# MicroMod-LoRa-1W-Function-Board-Waterfal.net
KiCad netlist of a schematic drawn in EAGLE
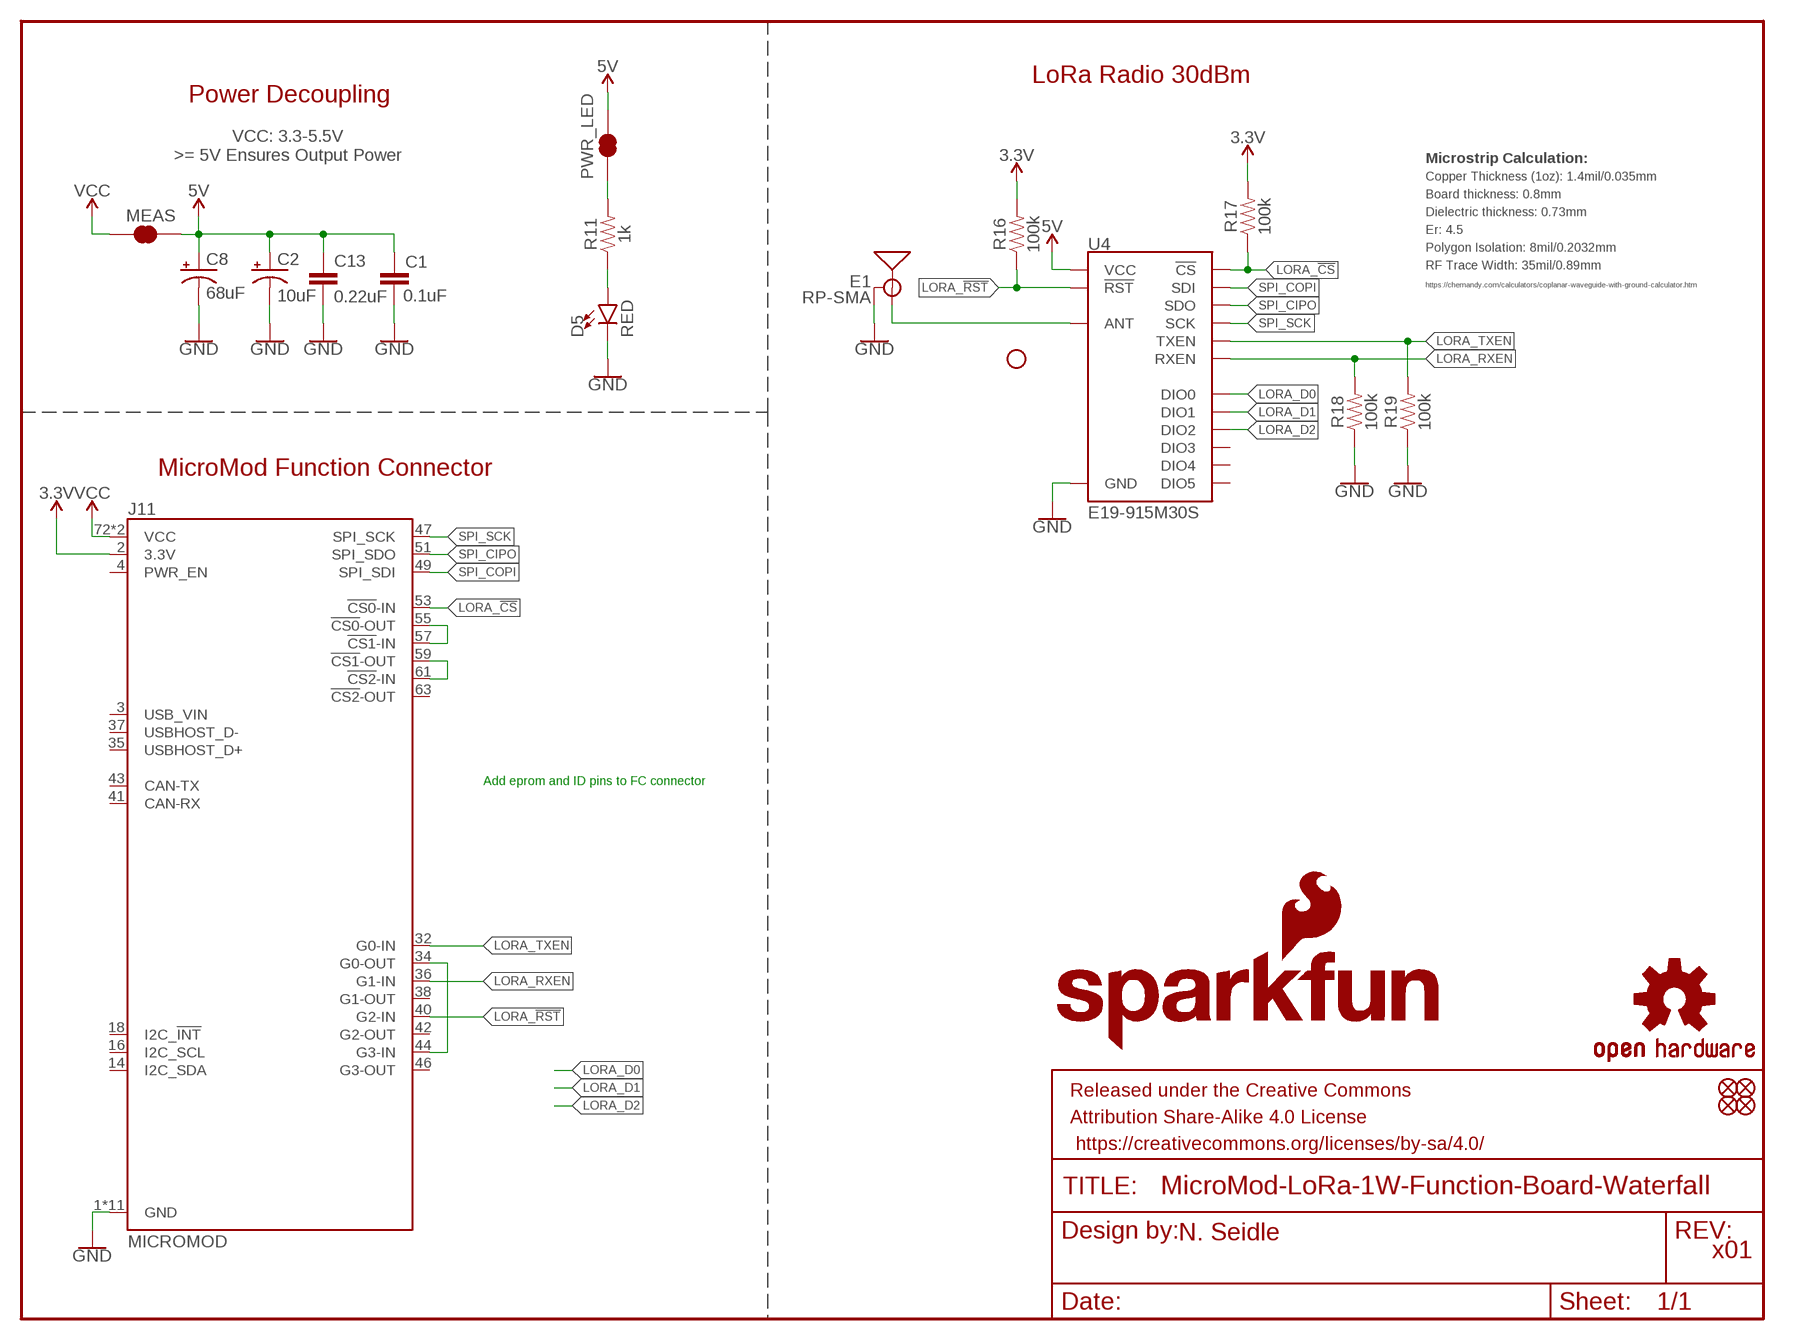
[diagram p0: schematic, sheet 1]

(export (version "E")
  (design (tool "Eeschema 10.0.6"))
  (components
    (comp (ref "C1")
      (value "0.1uF")
      (footprint "eagle-import:0603")
      (libsource (lib "eagle-import") (part "0.1UF-0603-25V-(+80/-20%)"))
    )
    (comp (ref "C2")
      (value "10uF")
      (footprint "eagle-import:EIA3216")
      (libsource (lib "eagle-import") (part "10UF-POLAR-EIA3216-16V-10%(TANT)"))
    )
    (comp (ref "C8")
      (value "68uF")
      (footprint "eagle-import:EIA3528")
      (libsource (lib "eagle-import") (part "68UF-POLAR-EIA3528-10V-10%(TANT)"))
    )
    (comp (ref "C13")
      (value "0.22uF")
      (footprint "eagle-import:0603")
      (libsource (lib "eagle-import") (part "0.22UF-0603-25V-10%"))
    )
    (comp (ref "D5")
      (value "RED")
      (footprint "eagle-import:LED-0603")
      (libsource (lib "eagle-import") (part "LED-RED0603"))
    )
    (comp (ref "E1")
      (value "RP-SMA")
      (footprint "eagle-import:SMA-EDGE-SMD")
      (libsource (lib "eagle-import") (part "ANTENNA-SMA-GROUNDEDEDGE_RPSMA_SMD"))
    )
    (comp (ref "FD1")
      (value "FIDUCIALUFIDUCIAL")
      (footprint "eagle-import:FIDUCIAL-MICRO")
      (libsource (lib "eagle-import") (part "FIDUCIALUFIDUCIAL"))
    )
    (comp (ref "FD2")
      (value "FIDUCIALUFIDUCIAL")
      (footprint "eagle-import:FIDUCIAL-MICRO")
      (libsource (lib "eagle-import") (part "FIDUCIALUFIDUCIAL"))
    )
    (comp (ref "FD3")
      (value "FIDUCIALUFIDUCIAL")
      (footprint "eagle-import:FIDUCIAL-MICRO")
      (libsource (lib "eagle-import") (part "FIDUCIALUFIDUCIAL"))
    )
    (comp (ref "FD4")
      (value "FIDUCIALUFIDUCIAL")
      (footprint "eagle-import:FIDUCIAL-MICRO")
      (libsource (lib "eagle-import") (part "FIDUCIALUFIDUCIAL"))
    )
    (comp (ref "FRAME2")
      (value "FRAME-LETTER")
      (footprint "eagle-import:CREATIVE_COMMONS")
      (libsource (lib "eagle-import") (part "FRAME-LETTER"))
    )
    (comp (ref "H1")
      (value "STAND-OFF")
      (footprint "eagle-import:STAND-OFF")
      (libsource (lib "eagle-import") (part "STAND-OFF"))
    )
    (comp (ref "J11")
      (value "MICROMOD")
      (footprint "eagle-import:M.2-CARD-E-22_FUNCTION_STANDARD")
      (libsource (lib "eagle-import") (part "MICROMOD"))
    )
    (comp (ref "LOGO1")
      (value "SFE_LOGO_NAME_FLAME.1_INCH")
      (footprint "eagle-import:SFE_LOGO_NAME_FLAME_.1")
      (libsource (lib "eagle-import") (part "SFE_LOGO_NAME_FLAME.1_INCH"))
    )
    (comp (ref "LOGO3")
      (value "OSHW-LOGOMINI")
      (footprint "eagle-import:OSHW-LOGO-MINI")
      (libsource (lib "eagle-import") (part "OSHW-LOGOMINI"))
    )
    (comp (ref "MEAS")
      (value "JUMPER-COMBO_2_NC_TRACE")
      (footprint "eagle-import:COMBO-JUMPER_2_NC_TRACE")
      (libsource (lib "eagle-import") (part "JUMPER-COMBO_2_NC_TRACE"))
    )
    (comp (ref "PWR_LED")
      (value "JUMPER-SMT_2_NC_TRACE_SILK")
      (footprint "eagle-import:SMT-JUMPER_2_NC_TRACE_SILK")
      (libsource (lib "eagle-import") (part "JUMPER-SMT_2_NC_TRACE_SILK"))
    )
    (comp (ref "R11")
      (value "1k")
      (footprint "eagle-import:0603")
      (libsource (lib "eagle-import") (part "1KOHM-0603-1/10W-1%"))
    )
    (comp (ref "R16")
      (value "100k")
      (footprint "eagle-import:0603")
      (libsource (lib "eagle-import") (part "100KOHM-0603-1/10W-1%"))
    )
    (comp (ref "R17")
      (value "100k")
      (footprint "eagle-import:0603")
      (libsource (lib "eagle-import") (part "100KOHM-0603-1/10W-1%"))
    )
    (comp (ref "R18")
      (value "100k")
      (footprint "eagle-import:0603")
      (libsource (lib "eagle-import") (part "100KOHM-0603-1/10W-1%"))
    )
    (comp (ref "R19")
      (value "100k")
      (footprint "eagle-import:0603")
      (libsource (lib "eagle-import") (part "100KOHM-0603-1/10W-1%"))
    )
    (comp (ref "U4")
      (value "E19-915M30S")
      (footprint "eagle-import:E19-915MS1W")
      (libsource (lib "eagle-import") (part "E19-915MS1W"))
    )
  )
  (nets
    (net (code "1") (name "/LORA_~{CS}") (class "Default")
      (node (ref "J11") (pin "53") (pinfunction "~{CS0}-IN_53") (pintype "bidirectional"))
      (node (ref "R17") (pin "1") (pinfunction "1_1") (pintype "passive"))
      (node (ref "U4") (pin "15") (pinfunction "~{CS}_15") (pintype "bidirectional"))
    )
    (net (code "2") (name "/LORA_~{RST}") (class "Default")
      (node (ref "J11") (pin "40") (pinfunction "G2-IN_40") (pintype "bidirectional"))
      (node (ref "R16") (pin "1") (pinfunction "1_1") (pintype "passive"))
      (node (ref "U4") (pin "8") (pinfunction "~{RST}_8") (pintype "bidirectional"))
    )
    (net (code "3") (name "3.3V") (class "Default")
      (node (ref "J11") (pin "2") (pinfunction "3.3V_2") (pintype "bidirectional"))
      (node (ref "R16") (pin "2") (pinfunction "2_2") (pintype "passive"))
      (node (ref "R17") (pin "2") (pinfunction "2_2") (pintype "passive"))
    )
    (net (code "4") (name "5V") (class "Default")
      (node (ref "C1") (pin "1") (pinfunction "1_1") (pintype "passive"))
      (node (ref "C13") (pin "1") (pinfunction "1_1") (pintype "passive"))
      (node (ref "C2") (pin "+") (pinfunction "+_+") (pintype "passive"))
      (node (ref "C8") (pin "A") (pinfunction "+_A") (pintype "passive"))
      (node (ref "MEAS") (pin "2") (pinfunction "2_2") (pintype "passive"))
      (node (ref "MEAS") (pin "4") (pinfunction "2_4") (pintype "passive"))
      (node (ref "PWR_LED") (pin "2") (pinfunction "2_2") (pintype "passive"))
      (node (ref "U4") (pin "11") (pinfunction "VCC_11") (pintype "bidirectional"))
    )
    (net (code "5") (name "GND") (class "Default")
      (node (ref "C1") (pin "2") (pinfunction "2_2") (pintype "passive"))
      (node (ref "C13") (pin "2") (pinfunction "2_2") (pintype "passive"))
      (node (ref "C2") (pin "-") (pinfunction "-_-") (pintype "passive"))
      (node (ref "C8") (pin "C") (pinfunction "-_C") (pintype "passive"))
      (node (ref "D5") (pin "C") (pinfunction "C_C") (pintype "passive"))
      (node (ref "E1") (pin "GND@0") (pinfunction "GND_GND@0") (pintype "bidirectional"))
      (node (ref "E1") (pin "GND@1") (pinfunction "GND_GND@1") (pintype "bidirectional"))
      (node (ref "J11") (pin "1") (pinfunction "GND_1") (pintype "bidirectional"))
      (node (ref "J11") (pin "33") (pinfunction "GND_33") (pintype "bidirectional"))
      (node (ref "J11") (pin "39") (pinfunction "GND_39") (pintype "bidirectional"))
      (node (ref "J11") (pin "45") (pinfunction "GND_45") (pintype "bidirectional"))
      (node (ref "J11") (pin "75") (pinfunction "GND_75") (pintype "bidirectional"))
      (node (ref "J11") (pin "GND1") (pinfunction "GND_GND1") (pintype "bidirectional"))
      (node (ref "J11") (pin "GND2") (pinfunction "GND_GND2") (pintype "bidirectional"))
      (node (ref "J11") (pin "GND3") (pinfunction "GND_GND3") (pintype "bidirectional"))
      (node (ref "J11") (pin "GND4") (pinfunction "GND_GND4") (pintype "bidirectional"))
      (node (ref "J11") (pin "GND5") (pinfunction "GND_GND5") (pintype "bidirectional"))
      (node (ref "J11") (pin "GND6") (pinfunction "GND_GND6") (pintype "bidirectional"))
      (node (ref "R18") (pin "1") (pinfunction "1_1") (pintype "passive"))
      (node (ref "R19") (pin "1") (pinfunction "1_1") (pintype "passive"))
      (node (ref "U4") (pin "1") (pinfunction "GND_1") (pintype "bidirectional"))
      (node (ref "U4") (pin "10") (pinfunction "GND_10") (pintype "bidirectional"))
      (node (ref "U4") (pin "18") (pinfunction "GND_18") (pintype "bidirectional"))
      (node (ref "U4") (pin "20") (pinfunction "GND_20") (pintype "bidirectional"))
      (node (ref "U4") (pin "21") (pinfunction "GND_21") (pintype "bidirectional"))
      (node (ref "U4") (pin "22") (pinfunction "GND_22") (pintype "bidirectional"))
      (node (ref "U4") (pin "9") (pinfunction "GND_9") (pintype "bidirectional"))
    )
    (net (code "6") (name "LORA_D0") (class "Default")
      (node (ref "U4") (pin "7") (pinfunction "DIO0_7") (pintype "bidirectional"))
    )
    (net (code "7") (name "LORA_D1") (class "Default")
      (node (ref "U4") (pin "6") (pinfunction "DIO1_6") (pintype "bidirectional"))
    )
    (net (code "8") (name "LORA_D2") (class "Default")
      (node (ref "U4") (pin "5") (pinfunction "DIO2_5") (pintype "bidirectional"))
    )
    (net (code "9") (name "LORA_RXEN") (class "Default")
      (node (ref "J11") (pin "36") (pinfunction "G1-IN_36") (pintype "bidirectional"))
      (node (ref "R18") (pin "2") (pinfunction "2_2") (pintype "passive"))
      (node (ref "U4") (pin "17") (pinfunction "RXEN_17") (pintype "bidirectional"))
    )
    (net (code "10") (name "LORA_TXEN") (class "Default")
      (node (ref "J11") (pin "32") (pinfunction "G0-IN_32") (pintype "bidirectional"))
      (node (ref "R19") (pin "2") (pinfunction "2_2") (pintype "passive"))
      (node (ref "U4") (pin "16") (pinfunction "TXEN_16") (pintype "bidirectional"))
    )
    (net (code "11") (name "Net-(D5-PadA)") (class "Default")
      (node (ref "D5") (pin "A") (pinfunction "A_A") (pintype "passive"))
      (node (ref "R11") (pin "1") (pinfunction "1_1") (pintype "passive"))
    )
    (net (code "12") (name "Net-(E1-SIGNAL)") (class "Default")
      (node (ref "E1") (pin "SIG") (pinfunction "SIGNAL_SIG") (pintype "bidirectional"))
      (node (ref "U4") (pin "19") (pinfunction "ANT_19") (pintype "bidirectional"))
    )
    (net (code "13") (name "Net-(J11-G0-OUT)") (class "Default")
      (node (ref "J11") (pin "34") (pinfunction "G0-OUT_34") (pintype "bidirectional"))
      (node (ref "J11") (pin "44") (pinfunction "G3-IN_44") (pintype "bidirectional"))
    )
    (net (code "14") (name "Net-(J11-~{CS0}-OUT)") (class "Default")
      (node (ref "J11") (pin "55") (pinfunction "~{CS0}-OUT_55") (pintype "bidirectional"))
      (node (ref "J11") (pin "57") (pinfunction "~{CS1}-IN_57") (pintype "bidirectional"))
    )
    (net (code "15") (name "Net-(J11-~{CS1}-OUT)") (class "Default")
      (node (ref "J11") (pin "59") (pinfunction "~{CS1}-OUT_59") (pintype "bidirectional"))
      (node (ref "J11") (pin "61") (pinfunction "~{CS2}-IN_61") (pintype "bidirectional"))
    )
    (net (code "16") (name "Net-(PWR_LED-Pad1)") (class "Default")
      (node (ref "PWR_LED") (pin "1") (pinfunction "1_1") (pintype "passive"))
      (node (ref "R11") (pin "2") (pinfunction "2_2") (pintype "passive"))
    )
    (net (code "17") (name "SPI_CIPO") (class "Default")
      (node (ref "J11") (pin "51") (pinfunction "SPI_SDO_51") (pintype "bidirectional"))
      (node (ref "U4") (pin "13") (pinfunction "SDO_13") (pintype "bidirectional"))
    )
    (net (code "18") (name "SPI_COPI") (class "Default")
      (node (ref "J11") (pin "49") (pinfunction "SPI_SDI_49") (pintype "bidirectional"))
      (node (ref "U4") (pin "14") (pinfunction "SDI_14") (pintype "bidirectional"))
    )
    (net (code "19") (name "SPI_SCK") (class "Default")
      (node (ref "J11") (pin "47") (pinfunction "SPI_SCK_47") (pintype "bidirectional"))
      (node (ref "U4") (pin "12") (pinfunction "SCK_12") (pintype "bidirectional"))
    )
    (net (code "20") (name "VCC") (class "Default")
      (node (ref "J11") (pin "72") (pinfunction "VCC_72") (pintype "bidirectional"))
      (node (ref "J11") (pin "74") (pinfunction "VCC_74") (pintype "bidirectional"))
      (node (ref "MEAS") (pin "1") (pinfunction "1_1") (pintype "passive"))
      (node (ref "MEAS") (pin "3") (pinfunction "1_3") (pintype "passive"))
    )
    (net (code "21") (name "unconnected-(J11-CAN-RX-Pad41)") (class "Default")
      (node (ref "J11") (pin "41") (pinfunction "CAN-RX_41") (pintype "bidirectional"))
    )
    (net (code "22") (name "unconnected-(J11-CAN-TX-Pad43)") (class "Default")
      (node (ref "J11") (pin "43") (pinfunction "CAN-TX_43") (pintype "bidirectional"))
    )
    (net (code "23") (name "unconnected-(J11-G1-OUT-Pad38)") (class "Default")
      (node (ref "J11") (pin "38") (pinfunction "G1-OUT_38") (pintype "bidirectional"))
    )
    (net (code "24") (name "unconnected-(J11-G2-OUT-Pad42)") (class "Default")
      (node (ref "J11") (pin "42") (pinfunction "G2-OUT_42") (pintype "bidirectional"))
    )
    (net (code "25") (name "unconnected-(J11-G3-OUT-Pad46)") (class "Default")
      (node (ref "J11") (pin "46") (pinfunction "G3-OUT_46") (pintype "bidirectional"))
    )
    (net (code "26") (name "unconnected-(J11-I2C_SCL-Pad16)") (class "Default")
      (node (ref "J11") (pin "16") (pinfunction "I2C_SCL_16") (pintype "bidirectional"))
    )
    (net (code "27") (name "unconnected-(J11-I2C_SDA-Pad14)") (class "Default")
      (node (ref "J11") (pin "14") (pinfunction "I2C_SDA_14") (pintype "bidirectional"))
    )
    (net (code "28") (name "unconnected-(J11-I2C_~{INT}-Pad18)") (class "Default")
      (node (ref "J11") (pin "18") (pinfunction "I2C_~{INT}_18") (pintype "bidirectional"))
    )
    (net (code "29") (name "unconnected-(J11-PWR_EN-Pad4)") (class "Default")
      (node (ref "J11") (pin "4") (pinfunction "PWR_EN_4") (pintype "bidirectional"))
    )
    (net (code "30") (name "unconnected-(J11-USBHOST_D+-Pad35)") (class "Default")
      (node (ref "J11") (pin "35") (pinfunction "USBHOST_D+_35") (pintype "bidirectional"))
    )
    (net (code "31") (name "unconnected-(J11-USBHOST_D--Pad37)") (class "Default")
      (node (ref "J11") (pin "37") (pinfunction "USBHOST_D-_37") (pintype "bidirectional"))
    )
    (net (code "32") (name "unconnected-(J11-USB_VIN-Pad3)") (class "Default")
      (node (ref "J11") (pin "3") (pinfunction "USB_VIN_3") (pintype "bidirectional"))
    )
    (net (code "33") (name "unconnected-(J11-~{CS2}-OUT-Pad63)") (class "Default")
      (node (ref "J11") (pin "63") (pinfunction "~{CS2}-OUT_63") (pintype "bidirectional"))
    )
    (net (code "34") (name "unconnected-(U4-DIO3-Pad4)") (class "Default")
      (node (ref "U4") (pin "4") (pinfunction "DIO3_4") (pintype "bidirectional"))
    )
    (net (code "35") (name "unconnected-(U4-DIO4-Pad3)") (class "Default")
      (node (ref "U4") (pin "3") (pinfunction "DIO4_3") (pintype "bidirectional"))
    )
    (net (code "36") (name "unconnected-(U4-DIO5-Pad2)") (class "Default")
      (node (ref "U4") (pin "2") (pinfunction "DIO5_2") (pintype "bidirectional"))
    )
  )
)
